# can.net
KiCad netlist of a schematic drawn in EAGLE
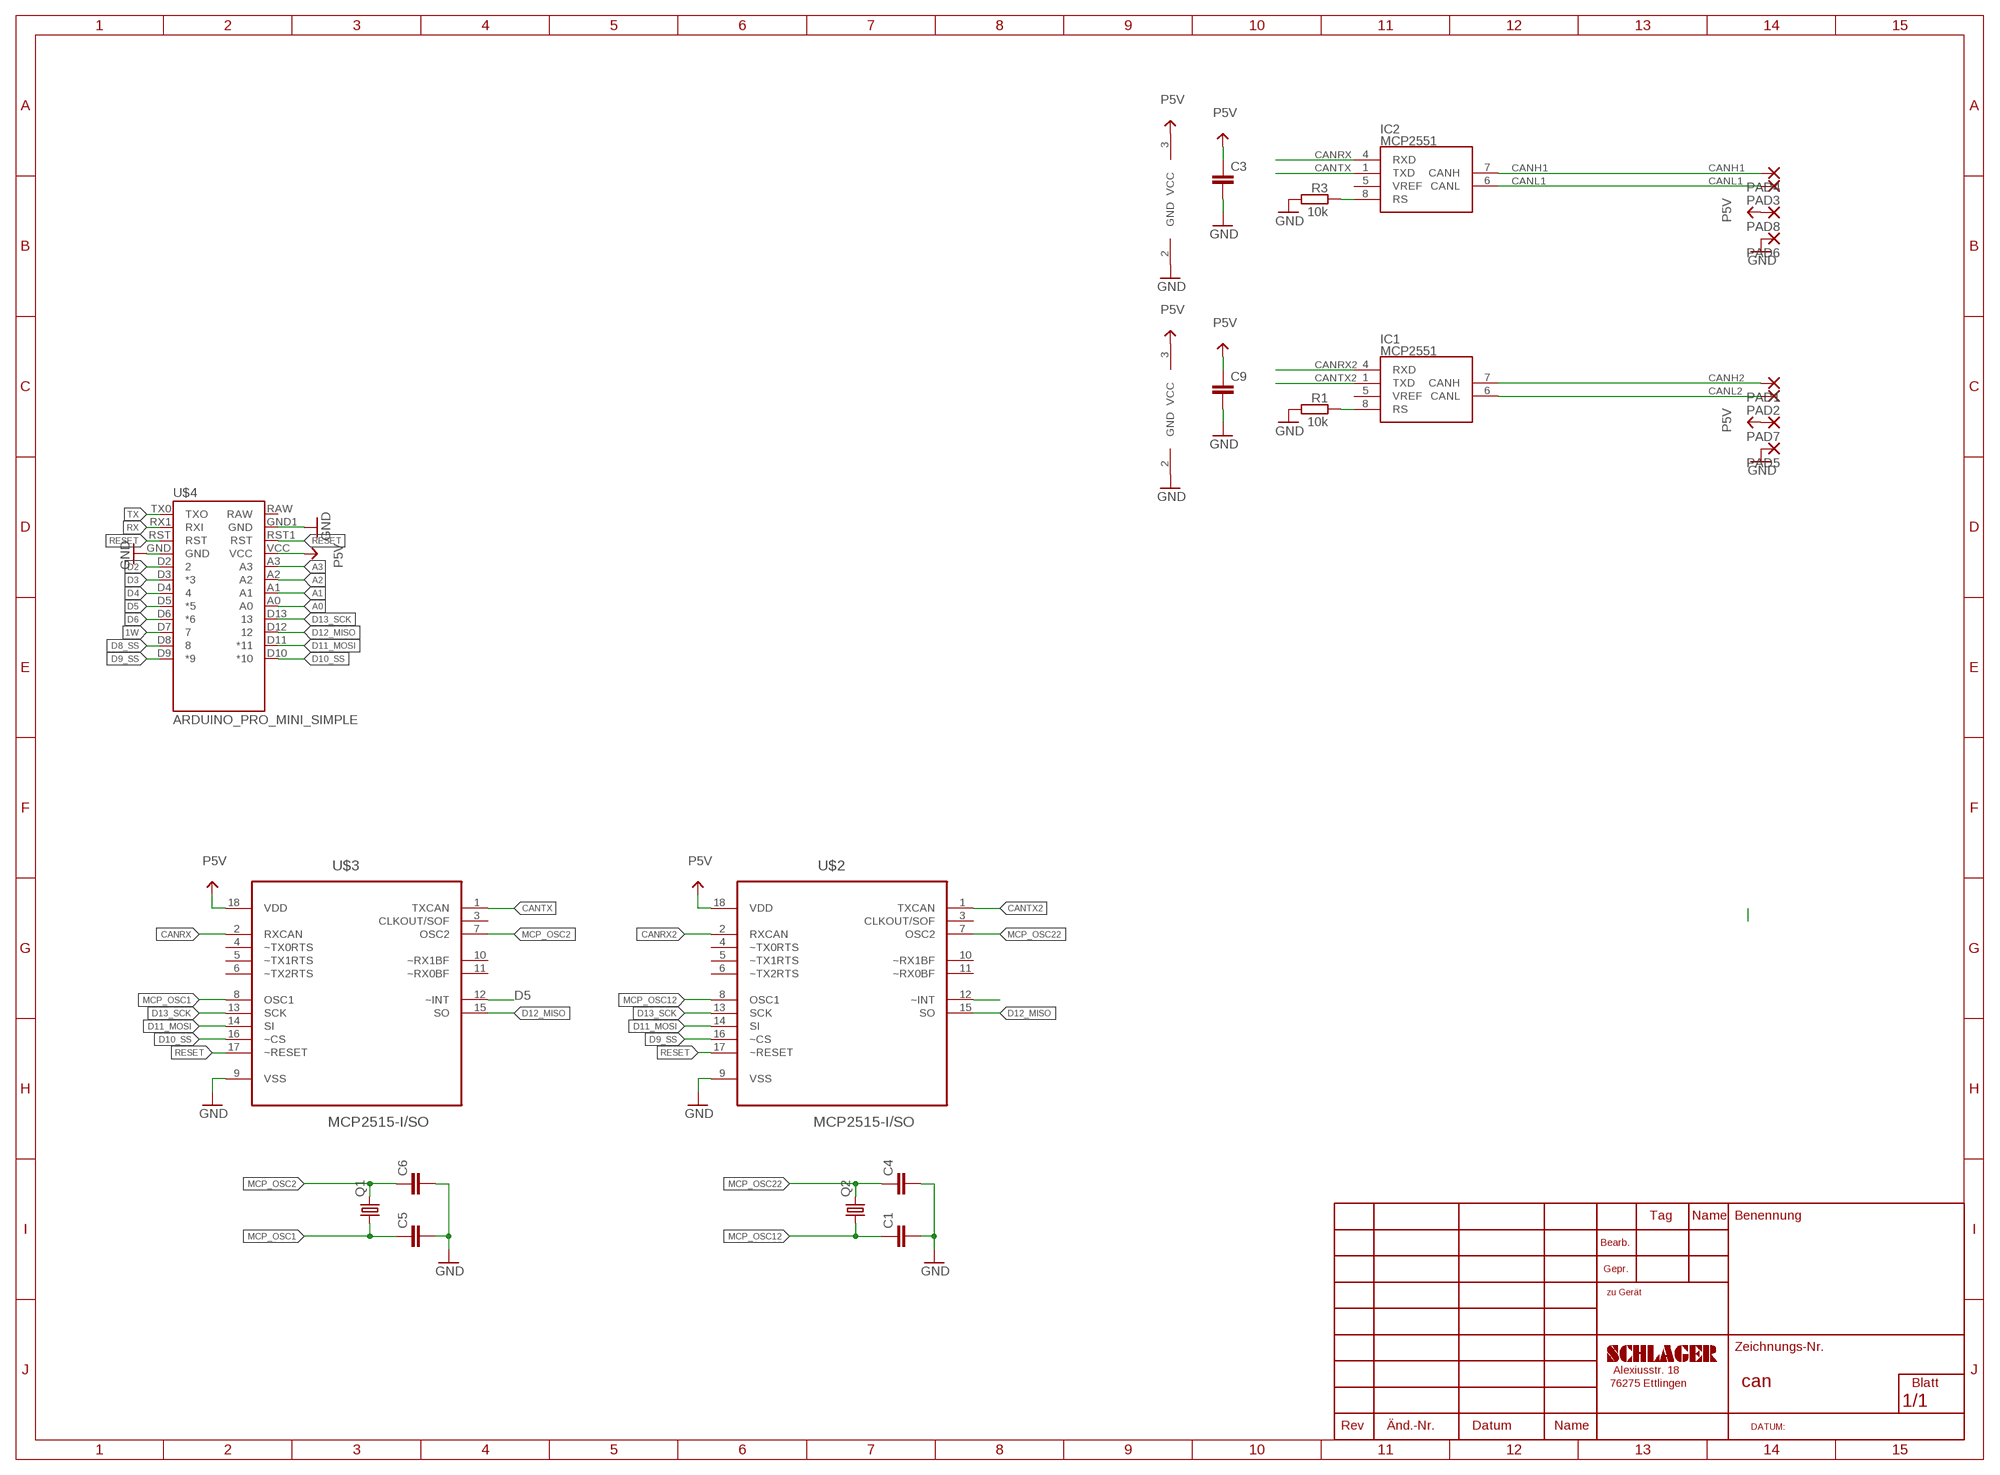
[diagram p0: schematic, sheet 1]

(export (version "E")
  (design (tool "Eeschema 10.0.6"))
  (components
    (comp (ref "C1")
      (value "C-EUC0805")
      (footprint "eagle-import:C0805")
      (libsource (lib "eagle-import") (part "C-EUC0805"))
    )
    (comp (ref "C3")
      (value "C-EUC0805")
      (footprint "eagle-import:C0805")
      (libsource (lib "eagle-import") (part "C-EUC0805"))
    )
    (comp (ref "C4")
      (value "C-EUC0805")
      (footprint "eagle-import:C0805")
      (libsource (lib "eagle-import") (part "C-EUC0805"))
    )
    (comp (ref "C5")
      (value "C-EUC0805")
      (footprint "eagle-import:C0805")
      (libsource (lib "eagle-import") (part "C-EUC0805"))
    )
    (comp (ref "C6")
      (value "C-EUC0805")
      (footprint "eagle-import:C0805")
      (libsource (lib "eagle-import") (part "C-EUC0805"))
    )
    (comp (ref "C9")
      (value "C-EUC0805")
      (footprint "eagle-import:C0805")
      (libsource (lib "eagle-import") (part "C-EUC0805"))
    )
    (comp (ref "IC1")
      (value "MCP2551")
      (footprint "eagle-import:SO-8")
      (libsource (lib "eagle-import") (part "MCP2551"))
    )
    (comp (ref "IC2")
      (value "MCP2551")
      (footprint "eagle-import:SO-8")
      (libsource (lib "eagle-import") (part "MCP2551"))
    )
    (comp (ref "PAD1")
      (value "SMD2")
      (footprint "eagle-import:SMD1,27-2,54")
      (libsource (lib "eagle-import") (part "SMD2"))
    )
    (comp (ref "PAD2")
      (value "SMD2")
      (footprint "eagle-import:SMD1,27-2,54")
      (libsource (lib "eagle-import") (part "SMD2"))
    )
    (comp (ref "PAD3")
      (value "SMD2")
      (footprint "eagle-import:SMD1,27-2,54")
      (libsource (lib "eagle-import") (part "SMD2"))
    )
    (comp (ref "PAD4")
      (value "SMD2")
      (footprint "eagle-import:SMD1,27-2,54")
      (libsource (lib "eagle-import") (part "SMD2"))
    )
    (comp (ref "PAD5")
      (value "SMD2")
      (footprint "eagle-import:SMD1,27-2,54")
      (libsource (lib "eagle-import") (part "SMD2"))
    )
    (comp (ref "PAD6")
      (value "SMD2")
      (footprint "eagle-import:SMD1,27-2,54")
      (libsource (lib "eagle-import") (part "SMD2"))
    )
    (comp (ref "PAD7")
      (value "SMD2")
      (footprint "eagle-import:SMD1,27-2,54")
      (libsource (lib "eagle-import") (part "SMD2"))
    )
    (comp (ref "PAD8")
      (value "SMD2")
      (footprint "eagle-import:SMD1,27-2,54")
      (libsource (lib "eagle-import") (part "SMD2"))
    )
    (comp (ref "Q1")
      (value "CRYSTALHC49S")
      (footprint "eagle-import:HC49_S")
      (libsource (lib "eagle-import") (part "CRYSTALHC49S"))
    )
    (comp (ref "Q2")
      (value "CRYSTALHC49S")
      (footprint "eagle-import:HC49_S")
      (libsource (lib "eagle-import") (part "CRYSTALHC49S"))
    )
    (comp (ref "R1")
      (value "10k")
      (footprint "eagle-import:R0603")
      (libsource (lib "eagle-import") (part "R-EU_R0603"))
    )
    (comp (ref "R3")
      (value "10k")
      (footprint "eagle-import:R0603")
      (libsource (lib "eagle-import") (part "R-EU_R0603"))
    )
    (comp (ref "U$2")
      (value "MCP2515-I/SO")
      (footprint "eagle-import:SOIC127P1034X264-18N")
      (libsource (lib "eagle-import") (part "MCP2515-I/SO"))
    )
    (comp (ref "U$3")
      (value "MCP2515-I/SO")
      (footprint "eagle-import:SOIC127P1034X264-18N")
      (libsource (lib "eagle-import") (part "MCP2515-I/SO"))
    )
    (comp (ref "U$4")
      (value "ARDUINO_PRO_MINI_SIMPLE")
      (footprint "eagle-import:PRO_MINI_SIMPLE")
      (libsource (lib "eagle-import") (part "ARDUINO_PRO_MINI_SIMPLE"))
    )
  )
  (nets
    (net (code "1") (name "/CANH1") (class "Default")
      (node (ref "IC2") (pin "7") (pinfunction "CANH_7") (pintype "bidirectional"))
      (node (ref "PAD4") (pin "1") (pinfunction "P_1") (pintype "passive"))
    )
    (net (code "2") (name "/CANH2") (class "Default")
      (node (ref "IC1") (pin "7") (pinfunction "CANH_7") (pintype "bidirectional"))
      (node (ref "PAD1") (pin "1") (pinfunction "P_1") (pintype "passive"))
    )
    (net (code "3") (name "/CANL1") (class "Default")
      (node (ref "IC2") (pin "6") (pinfunction "CANL_6") (pintype "bidirectional"))
      (node (ref "PAD3") (pin "1") (pinfunction "P_1") (pintype "passive"))
    )
    (net (code "4") (name "/CANL2") (class "Default")
      (node (ref "IC1") (pin "6") (pinfunction "CANL_6") (pintype "bidirectional"))
      (node (ref "PAD2") (pin "1") (pinfunction "P_1") (pintype "passive"))
    )
    (net (code "5") (name "1W") (class "Default")
      (node (ref "U$4") (pin "D7") (pinfunction "7_D7") (pintype "bidirectional"))
    )
    (net (code "6") (name "A0") (class "Default")
      (node (ref "U$4") (pin "A0") (pinfunction "A0_A0") (pintype "bidirectional"))
    )
    (net (code "7") (name "A1") (class "Default")
      (node (ref "U$4") (pin "A1") (pinfunction "A1_A1") (pintype "bidirectional"))
    )
    (net (code "8") (name "A2") (class "Default")
      (node (ref "U$4") (pin "A2") (pinfunction "A2_A2") (pintype "bidirectional"))
    )
    (net (code "9") (name "A3") (class "Default")
      (node (ref "U$4") (pin "A3") (pinfunction "A3_A3") (pintype "bidirectional"))
    )
    (net (code "10") (name "CANRX") (class "Default")
      (node (ref "IC2") (pin "4") (pinfunction "RXD_4") (pintype "bidirectional"))
      (node (ref "U$3") (pin "2") (pinfunction "RXCAN_2") (pintype "input"))
    )
    (net (code "11") (name "CANRX2") (class "Default")
      (node (ref "IC1") (pin "4") (pinfunction "RXD_4") (pintype "bidirectional"))
      (node (ref "U$2") (pin "2") (pinfunction "RXCAN_2") (pintype "input"))
    )
    (net (code "12") (name "CANTX") (class "Default")
      (node (ref "IC2") (pin "1") (pinfunction "TXD_1") (pintype "bidirectional"))
      (node (ref "U$3") (pin "1") (pinfunction "TXCAN_1") (pintype "output"))
    )
    (net (code "13") (name "CANTX2") (class "Default")
      (node (ref "IC1") (pin "1") (pinfunction "TXD_1") (pintype "bidirectional"))
      (node (ref "U$2") (pin "1") (pinfunction "TXCAN_1") (pintype "output"))
    )
    (net (code "14") (name "D2") (class "Default")
      (node (ref "U$4") (pin "D2") (pinfunction "2_D2") (pintype "bidirectional"))
    )
    (net (code "15") (name "D3") (class "Default")
      (node (ref "U$4") (pin "D3") (pinfunction "*3_D3") (pintype "bidirectional"))
    )
    (net (code "16") (name "D4") (class "Default")
      (node (ref "U$4") (pin "D4") (pinfunction "4_D4") (pintype "bidirectional"))
    )
    (net (code "17") (name "D5") (class "Default")
      (node (ref "U$3") (pin "12") (pinfunction "~{INT}_12") (pintype "output"))
      (node (ref "U$4") (pin "D5") (pinfunction "*5_D5") (pintype "bidirectional"))
    )
    (net (code "18") (name "D6") (class "Default")
      (node (ref "U$2") (pin "12") (pinfunction "~{INT}_12") (pintype "output"))
      (node (ref "U$4") (pin "D6") (pinfunction "*6_D6") (pintype "bidirectional"))
    )
    (net (code "19") (name "D8_SS") (class "Default")
      (node (ref "U$4") (pin "D8") (pinfunction "8_D8") (pintype "bidirectional"))
    )
    (net (code "20") (name "D9_SS") (class "Default")
      (node (ref "U$2") (pin "16") (pinfunction "~{CS}_16") (pintype "input"))
      (node (ref "U$4") (pin "D9") (pinfunction "*9_D9") (pintype "bidirectional"))
    )
    (net (code "21") (name "D10_SS") (class "Default")
      (node (ref "U$3") (pin "16") (pinfunction "~{CS}_16") (pintype "input"))
      (node (ref "U$4") (pin "D10") (pinfunction "*10_D10") (pintype "bidirectional"))
    )
    (net (code "22") (name "D11_MOSI") (class "Default")
      (node (ref "U$2") (pin "14") (pinfunction "SI_14") (pintype "input"))
      (node (ref "U$3") (pin "14") (pinfunction "SI_14") (pintype "input"))
      (node (ref "U$4") (pin "D11") (pinfunction "*11_D11") (pintype "bidirectional"))
    )
    (net (code "23") (name "D12_MISO") (class "Default")
      (node (ref "U$2") (pin "15") (pinfunction "SO_15") (pintype "output"))
      (node (ref "U$3") (pin "15") (pinfunction "SO_15") (pintype "output"))
      (node (ref "U$4") (pin "D12") (pinfunction "12_D12") (pintype "bidirectional"))
    )
    (net (code "24") (name "D13_SCK") (class "Default")
      (node (ref "U$2") (pin "13") (pinfunction "SCK_13") (pintype "input"))
      (node (ref "U$3") (pin "13") (pinfunction "SCK_13") (pintype "input"))
      (node (ref "U$4") (pin "D13") (pinfunction "13_D13") (pintype "bidirectional"))
    )
    (net (code "25") (name "GND") (class "Default")
      (node (ref "C1") (pin "2") (pinfunction "2_2") (pintype "passive"))
      (node (ref "C3") (pin "2") (pinfunction "2_2") (pintype "passive"))
      (node (ref "C4") (pin "2") (pinfunction "2_2") (pintype "passive"))
      (node (ref "C5") (pin "2") (pinfunction "2_2") (pintype "passive"))
      (node (ref "C6") (pin "2") (pinfunction "2_2") (pintype "passive"))
      (node (ref "C9") (pin "2") (pinfunction "2_2") (pintype "passive"))
      (node (ref "IC1") (pin "2") (pinfunction "GND_2") (pintype "power_in"))
      (node (ref "IC2") (pin "2") (pinfunction "GND_2") (pintype "power_in"))
      (node (ref "PAD5") (pin "1") (pinfunction "P_1") (pintype "passive"))
      (node (ref "PAD6") (pin "1") (pinfunction "P_1") (pintype "passive"))
      (node (ref "R1") (pin "2") (pinfunction "2_2") (pintype "passive"))
      (node (ref "R3") (pin "2") (pinfunction "2_2") (pintype "passive"))
      (node (ref "U$2") (pin "9") (pinfunction "VSS_9") (pintype "power_in"))
      (node (ref "U$3") (pin "9") (pinfunction "VSS_9") (pintype "power_in"))
      (node (ref "U$4") (pin "GND") (pinfunction "GND_GND") (pintype "bidirectional"))
      (node (ref "U$4") (pin "GND1") (pinfunction "GND_GND1") (pintype "bidirectional"))
    )
    (net (code "26") (name "MCP_OSC1") (class "Default")
      (node (ref "C5") (pin "1") (pinfunction "1_1") (pintype "passive"))
      (node (ref "Q1") (pin "1") (pinfunction "1_1") (pintype "passive"))
      (node (ref "U$3") (pin "8") (pinfunction "OSC1_8") (pintype "input"))
    )
    (net (code "27") (name "MCP_OSC2") (class "Default")
      (node (ref "C6") (pin "1") (pinfunction "1_1") (pintype "passive"))
      (node (ref "Q1") (pin "2") (pinfunction "2_2") (pintype "passive"))
      (node (ref "U$3") (pin "7") (pinfunction "OSC2_7") (pintype "output"))
    )
    (net (code "28") (name "MCP_OSC12") (class "Default")
      (node (ref "C1") (pin "1") (pinfunction "1_1") (pintype "passive"))
      (node (ref "Q2") (pin "1") (pinfunction "1_1") (pintype "passive"))
      (node (ref "U$2") (pin "8") (pinfunction "OSC1_8") (pintype "input"))
    )
    (net (code "29") (name "MCP_OSC22") (class "Default")
      (node (ref "C4") (pin "1") (pinfunction "1_1") (pintype "passive"))
      (node (ref "Q2") (pin "2") (pinfunction "2_2") (pintype "passive"))
      (node (ref "U$2") (pin "7") (pinfunction "OSC2_7") (pintype "output"))
    )
    (net (code "30") (name "Net-(IC1A-RS)") (class "Default")
      (node (ref "IC1") (pin "8") (pinfunction "RS_8") (pintype "bidirectional"))
      (node (ref "R1") (pin "1") (pinfunction "1_1") (pintype "passive"))
    )
    (net (code "31") (name "Net-(IC2A-RS)") (class "Default")
      (node (ref "IC2") (pin "8") (pinfunction "RS_8") (pintype "bidirectional"))
      (node (ref "R3") (pin "1") (pinfunction "1_1") (pintype "passive"))
    )
    (net (code "32") (name "P5V") (class "Default")
      (node (ref "C3") (pin "1") (pinfunction "1_1") (pintype "passive"))
      (node (ref "C9") (pin "1") (pinfunction "1_1") (pintype "passive"))
      (node (ref "IC1") (pin "3") (pinfunction "VCC_3") (pintype "power_in"))
      (node (ref "IC2") (pin "3") (pinfunction "VCC_3") (pintype "power_in"))
      (node (ref "PAD7") (pin "1") (pinfunction "P_1") (pintype "passive"))
      (node (ref "PAD8") (pin "1") (pinfunction "P_1") (pintype "passive"))
      (node (ref "U$2") (pin "18") (pinfunction "VDD_18") (pintype "power_in"))
      (node (ref "U$3") (pin "18") (pinfunction "VDD_18") (pintype "power_in"))
      (node (ref "U$4") (pin "VCC") (pinfunction "VCC_VCC") (pintype "bidirectional"))
    )
    (net (code "33") (name "RESET") (class "Default")
      (node (ref "U$2") (pin "17") (pinfunction "~{RESET}_17") (pintype "input"))
      (node (ref "U$3") (pin "17") (pinfunction "~{RESET}_17") (pintype "input"))
      (node (ref "U$4") (pin "RST") (pinfunction "RST_RST") (pintype "bidirectional"))
      (node (ref "U$4") (pin "RST1") (pinfunction "RST_RST1") (pintype "bidirectional"))
    )
    (net (code "34") (name "RX") (class "Default")
      (node (ref "U$4") (pin "RX1") (pinfunction "RXI_RX1") (pintype "bidirectional"))
    )
    (net (code "35") (name "TX") (class "Default")
      (node (ref "U$4") (pin "TX0") (pinfunction "TXO_TX0") (pintype "bidirectional"))
    )
    (net (code "36") (name "unconnected-(IC1A-VREF-Pad5)") (class "Default")
      (node (ref "IC1") (pin "5") (pinfunction "VREF_5") (pintype "bidirectional"))
    )
    (net (code "37") (name "unconnected-(IC2A-VREF-Pad5)") (class "Default")
      (node (ref "IC2") (pin "5") (pinfunction "VREF_5") (pintype "bidirectional"))
    )
    (net (code "38") (name "unconnected-(U$2-CLKOUT{slash}SOF-Pad3)") (class "Default")
      (node (ref "U$2") (pin "3") (pinfunction "CLKOUT/SOF_3") (pintype "output"))
    )
    (net (code "39") (name "unconnected-(U$2-~{RX0BF}-Pad11)") (class "Default")
      (node (ref "U$2") (pin "11") (pinfunction "~{RX0BF}_11") (pintype "output"))
    )
    (net (code "40") (name "unconnected-(U$2-~{RX1BF}-Pad10)") (class "Default")
      (node (ref "U$2") (pin "10") (pinfunction "~{RX1BF}_10") (pintype "output"))
    )
    (net (code "41") (name "unconnected-(U$2-~{TX0RTS}-Pad4)") (class "Default")
      (node (ref "U$2") (pin "4") (pinfunction "~{TX0RTS}_4") (pintype "input"))
    )
    (net (code "42") (name "unconnected-(U$2-~{TX1RTS}-Pad5)") (class "Default")
      (node (ref "U$2") (pin "5") (pinfunction "~{TX1RTS}_5") (pintype "input"))
    )
    (net (code "43") (name "unconnected-(U$2-~{TX2RTS}-Pad6)") (class "Default")
      (node (ref "U$2") (pin "6") (pinfunction "~{TX2RTS}_6") (pintype "input"))
    )
    (net (code "44") (name "unconnected-(U$3-CLKOUT{slash}SOF-Pad3)") (class "Default")
      (node (ref "U$3") (pin "3") (pinfunction "CLKOUT/SOF_3") (pintype "output"))
    )
    (net (code "45") (name "unconnected-(U$3-~{RX0BF}-Pad11)") (class "Default")
      (node (ref "U$3") (pin "11") (pinfunction "~{RX0BF}_11") (pintype "output"))
    )
    (net (code "46") (name "unconnected-(U$3-~{RX1BF}-Pad10)") (class "Default")
      (node (ref "U$3") (pin "10") (pinfunction "~{RX1BF}_10") (pintype "output"))
    )
    (net (code "47") (name "unconnected-(U$3-~{TX0RTS}-Pad4)") (class "Default")
      (node (ref "U$3") (pin "4") (pinfunction "~{TX0RTS}_4") (pintype "input"))
    )
    (net (code "48") (name "unconnected-(U$3-~{TX1RTS}-Pad5)") (class "Default")
      (node (ref "U$3") (pin "5") (pinfunction "~{TX1RTS}_5") (pintype "input"))
    )
    (net (code "49") (name "unconnected-(U$3-~{TX2RTS}-Pad6)") (class "Default")
      (node (ref "U$3") (pin "6") (pinfunction "~{TX2RTS}_6") (pintype "input"))
    )
    (net (code "50") (name "unconnected-(U$4-PadRAW)") (class "Default")
      (node (ref "U$4") (pin "RAW") (pinfunction "RAW_RAW") (pintype "bidirectional"))
    )
  )
)
